# Connecteur.net
KiCad netlist of a schematic drawn in Altium Designer
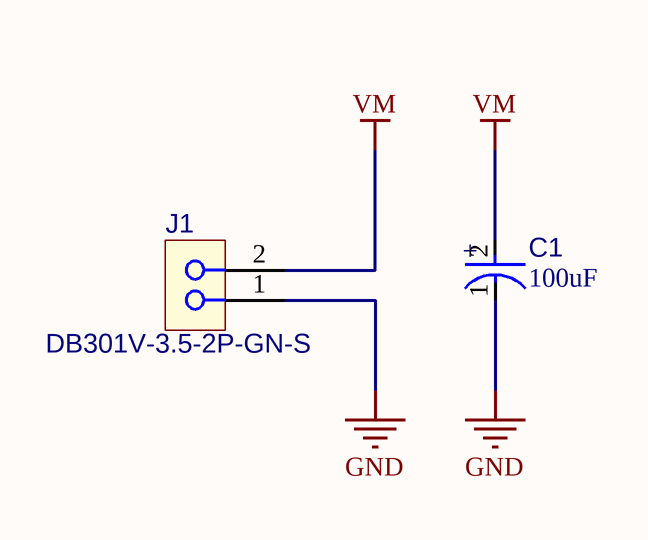
[diagram p0: Connecteur.SchDoc]

(export (version "E")
  (design (tool "Eeschema 10.0.6"))
  (components
    (comp (ref "C1")
      (value "100uF")
      (footprint "C_EL_D10MM-L11MM")
      (description "Capacitor type EL")
      (libsource (lib "243-436-MikoBus-DrvMot") (part "capacitor_EL"))
    )
    (comp (ref "J1")
      (value "DB301V-3.5-2P-GN-S")
      (footprint "CONN_TERM_BLOCK_2POS_3mm5")
      (description "CONN TERM BLOCK 2POS 3.5mm pitch")
      (libsource (lib "TEP_243-AltiumLIB-Conn-TP-MH") (part "CONN-3MM5-2POS-TERM-BLOCK"))
    )
  )
  (nets
    (net (code "1") (name "GND") (class "Default")
      (node (ref "C1") (pin "1") (pinfunction "C_1") (pintype "passive"))
      (node (ref "J1") (pin "1") (pinfunction "1_1") (pintype "passive"))
    )
    (net (code "2") (name "VM") (class "Default")
      (node (ref "C1") (pin "2") (pinfunction "A_2") (pintype "passive"))
      (node (ref "J1") (pin "2") (pinfunction "2_2") (pintype "passive"))
    )
  )
)
